# se8.net
KiCad netlist of a schematic drawn in EAGLE
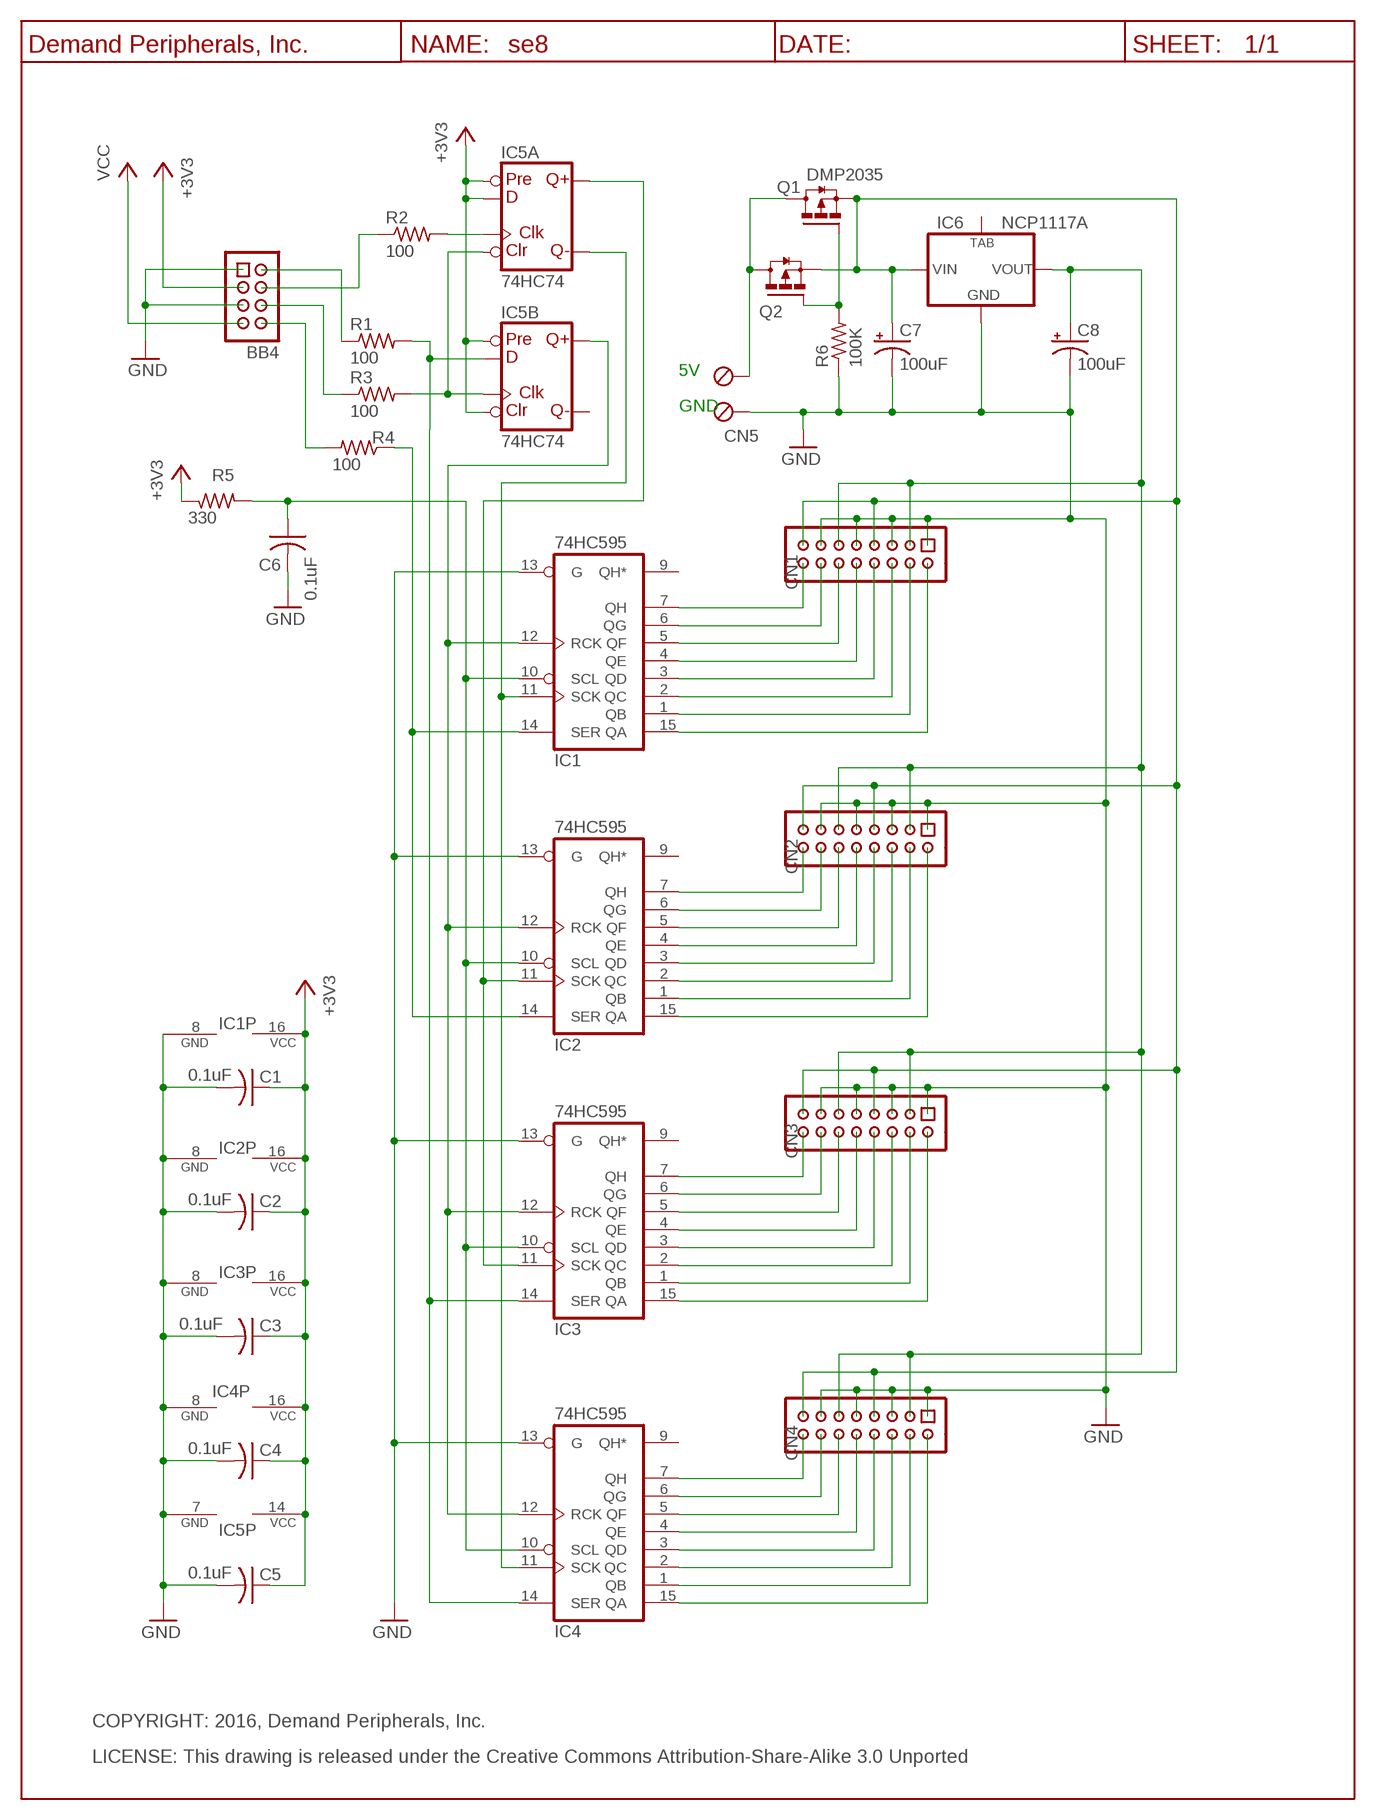
[diagram p0: schematic, sheet 1]

(export (version "E")
  (design (tool "Eeschema 10.0.6"))
  (components
    (comp (ref "BB4")
      (value "BB4 Header")
      (footprint "eagle-import:HDR-4X2")
      (libsource (lib "eagle-import") (part "HDR-4X2-SHR"))
    )
    (comp (ref "C1")
      (value "0.1uF")
      (footprint "eagle-import:C0603")
      (libsource (lib "eagle-import") (part "C0.1UF_C0603"))
    )
    (comp (ref "C2")
      (value "0.1uF")
      (footprint "eagle-import:C0603")
      (libsource (lib "eagle-import") (part "C0.1UF_C0603"))
    )
    (comp (ref "C3")
      (value "0.1uF")
      (footprint "eagle-import:C0603")
      (libsource (lib "eagle-import") (part "C0.1UF_C0603"))
    )
    (comp (ref "C4")
      (value "0.1uF")
      (footprint "eagle-import:C0603")
      (libsource (lib "eagle-import") (part "C0.1UF_C0603"))
    )
    (comp (ref "C5")
      (value "0.1uF")
      (footprint "eagle-import:C0603")
      (libsource (lib "eagle-import") (part "C0.1UF_C0603"))
    )
    (comp (ref "C6")
      (value "0.1uF")
      (footprint "eagle-import:C0603")
      (libsource (lib "eagle-import") (part "C0.1UF_C0603"))
    )
    (comp (ref "C7")
      (value "100uF")
      (footprint "eagle-import:E3.5-8")
      (libsource (lib "eagle-import") (part "C100UF35V_E3.5-8"))
    )
    (comp (ref "C8")
      (value "100uF")
      (footprint "eagle-import:E3.5-8")
      (libsource (lib "eagle-import") (part "C100UF35V_E3.5-8"))
    )
    (comp (ref "CN1")
      (value "HDR-8X2-SHR")
      (footprint "eagle-import:HDR-8X2")
      (libsource (lib "eagle-import") (part "HDR-8X2-SHR"))
    )
    (comp (ref "CN2")
      (value "HDR-8X2-SHR")
      (footprint "eagle-import:HDR-8X2")
      (libsource (lib "eagle-import") (part "HDR-8X2-SHR"))
    )
    (comp (ref "CN3")
      (value "HDR-8X2-SHR")
      (footprint "eagle-import:HDR-8X2")
      (libsource (lib "eagle-import") (part "HDR-8X2-SHR"))
    )
    (comp (ref "CN4")
      (value "HDR-8X2-SHR")
      (footprint "eagle-import:HDR-8X2")
      (libsource (lib "eagle-import") (part "HDR-8X2-SHR"))
    )
    (comp (ref "CN5")
      (value "TBLK-5.08-X2")
      (footprint "eagle-import:TBLK-5.08-X2")
      (libsource (lib "eagle-import") (part "TBLK-5.08-X2"))
    )
    (comp (ref "IC1")
      (value "74HC595")
      (footprint "eagle-import:SO16")
      (libsource (lib "eagle-import") (part "74595"))
    )
    (comp (ref "IC2")
      (value "74HC595")
      (footprint "eagle-import:SO16")
      (libsource (lib "eagle-import") (part "74595"))
    )
    (comp (ref "IC3")
      (value "74HC595")
      (footprint "eagle-import:SO16")
      (libsource (lib "eagle-import") (part "74595"))
    )
    (comp (ref "IC4")
      (value "74HC595")
      (footprint "eagle-import:SO16")
      (libsource (lib "eagle-import") (part "74595"))
    )
    (comp (ref "IC5")
      (value "74HC74")
      (footprint "eagle-import:SO14")
      (libsource (lib "eagle-import") (part "74AHC74"))
    )
    (comp (ref "IC6")
      (value "NCP1117A")
      (footprint "eagle-import:SOT223")
      (libsource (lib "eagle-import") (part "LM1117A"))
    )
    (comp (ref "Q1")
      (value "DMP2035")
      (footprint "eagle-import:SOT23")
      (libsource (lib "eagle-import") (part "DMP2035"))
    )
    (comp (ref "Q2")
      (value "DMP2035")
      (footprint "eagle-import:SOT23")
      (libsource (lib "eagle-import") (part "DMP2035"))
    )
    (comp (ref "R1")
      (value "100")
      (footprint "eagle-import:R0603")
      (libsource (lib "eagle-import") (part "R100_R0603"))
    )
    (comp (ref "R2")
      (value "100")
      (footprint "eagle-import:R0603")
      (libsource (lib "eagle-import") (part "R100_R0603"))
    )
    (comp (ref "R3")
      (value "100")
      (footprint "eagle-import:R0603")
      (libsource (lib "eagle-import") (part "R100_R0603"))
    )
    (comp (ref "R4")
      (value "100")
      (footprint "eagle-import:R0603")
      (libsource (lib "eagle-import") (part "R100_R0603"))
    )
    (comp (ref "R5")
      (value "330")
      (footprint "eagle-import:R0603")
      (libsource (lib "eagle-import") (part "R330_R0603"))
    )
    (comp (ref "R6")
      (value "100K")
      (footprint "eagle-import:R0603")
      (libsource (lib "eagle-import") (part "R100K_R0603"))
    )
    (comp (ref "U$2")
      (value "DP_FRAME_P")
      (footprint "eagle-import:P_FRAME")
      (libsource (lib "eagle-import") (part "DP_FRAME_P"))
    )
  )
  (nets
    (net (code "1") (name "+3V3") (class "Default")
      (node (ref "BB4") (pin "3") (pinfunction "3_3") (pintype "passive"))
      (node (ref "C1") (pin "1") (pinfunction "1_1") (pintype "passive"))
      (node (ref "C2") (pin "1") (pinfunction "1_1") (pintype "passive"))
      (node (ref "C3") (pin "1") (pinfunction "1_1") (pintype "passive"))
      (node (ref "C4") (pin "1") (pinfunction "1_1") (pintype "passive"))
      (node (ref "C5") (pin "1") (pinfunction "1_1") (pintype "passive"))
      (node (ref "IC1") (pin "16") (pinfunction "VCC_16") (pintype "power_in"))
      (node (ref "IC2") (pin "16") (pinfunction "VCC_16") (pintype "power_in"))
      (node (ref "IC3") (pin "16") (pinfunction "VCC_16") (pintype "power_in"))
      (node (ref "IC4") (pin "16") (pinfunction "VCC_16") (pintype "power_in"))
      (node (ref "IC5") (pin "10") (pinfunction "PRE_10") (pintype "input"))
      (node (ref "IC5") (pin "13") (pinfunction "CLR_13") (pintype "input"))
      (node (ref "IC5") (pin "14") (pinfunction "VCC_14") (pintype "power_in"))
      (node (ref "IC5") (pin "2") (pinfunction "D_2") (pintype "input"))
      (node (ref "IC5") (pin "4") (pinfunction "PRE_4") (pintype "input"))
      (node (ref "R5") (pin "1") (pinfunction "1_1") (pintype "passive"))
    )
    (net (code "2") (name "GND") (class "Default")
      (node (ref "BB4") (pin "1") (pinfunction "1_1") (pintype "passive"))
      (node (ref "BB4") (pin "5") (pinfunction "5_5") (pintype "passive"))
      (node (ref "C1") (pin "2") (pinfunction "2_2") (pintype "passive"))
      (node (ref "C2") (pin "2") (pinfunction "2_2") (pintype "passive"))
      (node (ref "C3") (pin "2") (pinfunction "2_2") (pintype "passive"))
      (node (ref "C4") (pin "2") (pinfunction "2_2") (pintype "passive"))
      (node (ref "C5") (pin "2") (pinfunction "2_2") (pintype "passive"))
      (node (ref "C6") (pin "2") (pinfunction "2_2") (pintype "passive"))
      (node (ref "C7") (pin "-") (pinfunction "-_-") (pintype "passive"))
      (node (ref "C8") (pin "-") (pinfunction "-_-") (pintype "passive"))
      (node (ref "CN1") (pin "1") (pinfunction "1_1") (pintype "passive"))
      (node (ref "CN1") (pin "13") (pinfunction "13_13") (pintype "passive"))
      (node (ref "CN1") (pin "5") (pinfunction "5_5") (pintype "passive"))
      (node (ref "CN1") (pin "9") (pinfunction "9_9") (pintype "passive"))
      (node (ref "CN2") (pin "1") (pinfunction "1_1") (pintype "passive"))
      (node (ref "CN2") (pin "13") (pinfunction "13_13") (pintype "passive"))
      (node (ref "CN2") (pin "5") (pinfunction "5_5") (pintype "passive"))
      (node (ref "CN2") (pin "9") (pinfunction "9_9") (pintype "passive"))
      (node (ref "CN3") (pin "1") (pinfunction "1_1") (pintype "passive"))
      (node (ref "CN3") (pin "13") (pinfunction "13_13") (pintype "passive"))
      (node (ref "CN3") (pin "5") (pinfunction "5_5") (pintype "passive"))
      (node (ref "CN3") (pin "9") (pinfunction "9_9") (pintype "passive"))
      (node (ref "CN4") (pin "1") (pinfunction "1_1") (pintype "passive"))
      (node (ref "CN4") (pin "13") (pinfunction "13_13") (pintype "passive"))
      (node (ref "CN4") (pin "5") (pinfunction "5_5") (pintype "passive"))
      (node (ref "CN4") (pin "9") (pinfunction "9_9") (pintype "passive"))
      (node (ref "CN5") (pin "1") (pinfunction "KL_1") (pintype "passive"))
      (node (ref "IC1") (pin "13") (pinfunction "G_13") (pintype "input"))
      (node (ref "IC1") (pin "8") (pinfunction "GND_8") (pintype "power_in"))
      (node (ref "IC2") (pin "13") (pinfunction "G_13") (pintype "input"))
      (node (ref "IC2") (pin "8") (pinfunction "GND_8") (pintype "power_in"))
      (node (ref "IC3") (pin "13") (pinfunction "G_13") (pintype "input"))
      (node (ref "IC3") (pin "8") (pinfunction "GND_8") (pintype "power_in"))
      (node (ref "IC4") (pin "13") (pinfunction "G_13") (pintype "input"))
      (node (ref "IC4") (pin "8") (pinfunction "GND_8") (pintype "power_in"))
      (node (ref "IC5") (pin "7") (pinfunction "GND_7") (pintype "power_in"))
      (node (ref "IC6") (pin "1") (pinfunction "GND_1") (pintype "input"))
      (node (ref "R6") (pin "1") (pinfunction "1_1") (pintype "passive"))
    )
    (net (code "3") (name "Net-(BB4-Pad2)") (class "Default")
      (node (ref "BB4") (pin "2") (pinfunction "2_2") (pintype "passive"))
      (node (ref "R1") (pin "1") (pinfunction "1_1") (pintype "passive"))
    )
    (net (code "4") (name "Net-(BB4-Pad4)") (class "Default")
      (node (ref "BB4") (pin "4") (pinfunction "4_4") (pintype "passive"))
      (node (ref "R2") (pin "1") (pinfunction "1_1") (pintype "passive"))
    )
    (net (code "5") (name "Net-(BB4-Pad6)") (class "Default")
      (node (ref "BB4") (pin "6") (pinfunction "6_6") (pintype "passive"))
      (node (ref "R3") (pin "1") (pinfunction "1_1") (pintype "passive"))
    )
    (net (code "6") (name "Net-(BB4-Pad8)") (class "Default")
      (node (ref "BB4") (pin "8") (pinfunction "8_8") (pintype "passive"))
      (node (ref "R4") (pin "2") (pinfunction "2_2") (pintype "passive"))
    )
    (net (code "7") (name "Net-(CN5-KL1)") (class "Default")
      (node (ref "CN5") (pin "2") (pinfunction "KL1_2") (pintype "passive"))
      (node (ref "Q1") (pin "2") (pinfunction "D_2") (pintype "passive"))
      (node (ref "Q2") (pin "2") (pinfunction "D_2") (pintype "passive"))
    )
    (net (code "8") (name "Net-(IC1A-QA)") (class "Default")
      (node (ref "CN1") (pin "2") (pinfunction "2_2") (pintype "passive"))
      (node (ref "IC1") (pin "15") (pinfunction "QA_15") (pintype "tri_state"))
    )
    (net (code "9") (name "Net-(IC1A-QB)") (class "Default")
      (node (ref "CN1") (pin "4") (pinfunction "4_4") (pintype "passive"))
      (node (ref "IC1") (pin "1") (pinfunction "QB_1") (pintype "tri_state"))
    )
    (net (code "10") (name "Net-(IC1A-QC)") (class "Default")
      (node (ref "CN1") (pin "6") (pinfunction "6_6") (pintype "passive"))
      (node (ref "IC1") (pin "2") (pinfunction "QC_2") (pintype "tri_state"))
    )
    (net (code "11") (name "Net-(IC1A-QD)") (class "Default")
      (node (ref "CN1") (pin "8") (pinfunction "8_8") (pintype "passive"))
      (node (ref "IC1") (pin "3") (pinfunction "QD_3") (pintype "tri_state"))
    )
    (net (code "12") (name "Net-(IC1A-QE)") (class "Default")
      (node (ref "CN1") (pin "10") (pinfunction "10_10") (pintype "passive"))
      (node (ref "IC1") (pin "4") (pinfunction "QE_4") (pintype "tri_state"))
    )
    (net (code "13") (name "Net-(IC1A-QF)") (class "Default")
      (node (ref "CN1") (pin "12") (pinfunction "12_12") (pintype "passive"))
      (node (ref "IC1") (pin "5") (pinfunction "QF_5") (pintype "tri_state"))
    )
    (net (code "14") (name "Net-(IC1A-QG)") (class "Default")
      (node (ref "CN1") (pin "14") (pinfunction "14_14") (pintype "passive"))
      (node (ref "IC1") (pin "6") (pinfunction "QG_6") (pintype "tri_state"))
    )
    (net (code "15") (name "Net-(IC1A-QH)") (class "Default")
      (node (ref "CN1") (pin "16") (pinfunction "16_16") (pintype "passive"))
      (node (ref "IC1") (pin "7") (pinfunction "QH_7") (pintype "tri_state"))
    )
    (net (code "16") (name "Net-(IC1A-RCK)") (class "Default")
      (node (ref "IC1") (pin "12") (pinfunction "RCK_12") (pintype "input"))
      (node (ref "IC2") (pin "12") (pinfunction "RCK_12") (pintype "input"))
      (node (ref "IC3") (pin "12") (pinfunction "RCK_12") (pintype "input"))
      (node (ref "IC4") (pin "12") (pinfunction "RCK_12") (pintype "input"))
      (node (ref "IC5") (pin "9") (pinfunction "Q_9") (pintype "output"))
    )
    (net (code "17") (name "Net-(IC1A-SCK)") (class "Default")
      (node (ref "IC1") (pin "11") (pinfunction "SCK_11") (pintype "input"))
      (node (ref "IC4") (pin "11") (pinfunction "SCK_11") (pintype "input"))
      (node (ref "IC5") (pin "6") (pinfunction "~{Q}_6") (pintype "output"))
    )
    (net (code "18") (name "Net-(IC1A-SCL)") (class "Default")
      (node (ref "C6") (pin "1") (pinfunction "1_1") (pintype "passive"))
      (node (ref "IC1") (pin "10") (pinfunction "SCL_10") (pintype "input"))
      (node (ref "IC2") (pin "10") (pinfunction "SCL_10") (pintype "input"))
      (node (ref "IC3") (pin "10") (pinfunction "SCL_10") (pintype "input"))
      (node (ref "IC4") (pin "10") (pinfunction "SCL_10") (pintype "input"))
      (node (ref "R5") (pin "2") (pinfunction "2_2") (pintype "passive"))
    )
    (net (code "19") (name "Net-(IC1A-SER)") (class "Default")
      (node (ref "IC1") (pin "14") (pinfunction "SER_14") (pintype "input"))
      (node (ref "IC2") (pin "14") (pinfunction "SER_14") (pintype "input"))
      (node (ref "R4") (pin "1") (pinfunction "1_1") (pintype "passive"))
    )
    (net (code "20") (name "Net-(IC2A-QA)") (class "Default")
      (node (ref "CN2") (pin "2") (pinfunction "2_2") (pintype "passive"))
      (node (ref "IC2") (pin "15") (pinfunction "QA_15") (pintype "tri_state"))
    )
    (net (code "21") (name "Net-(IC2A-QB)") (class "Default")
      (node (ref "CN2") (pin "4") (pinfunction "4_4") (pintype "passive"))
      (node (ref "IC2") (pin "1") (pinfunction "QB_1") (pintype "tri_state"))
    )
    (net (code "22") (name "Net-(IC2A-QC)") (class "Default")
      (node (ref "CN2") (pin "6") (pinfunction "6_6") (pintype "passive"))
      (node (ref "IC2") (pin "2") (pinfunction "QC_2") (pintype "tri_state"))
    )
    (net (code "23") (name "Net-(IC2A-QD)") (class "Default")
      (node (ref "CN2") (pin "8") (pinfunction "8_8") (pintype "passive"))
      (node (ref "IC2") (pin "3") (pinfunction "QD_3") (pintype "tri_state"))
    )
    (net (code "24") (name "Net-(IC2A-QE)") (class "Default")
      (node (ref "CN2") (pin "10") (pinfunction "10_10") (pintype "passive"))
      (node (ref "IC2") (pin "4") (pinfunction "QE_4") (pintype "tri_state"))
    )
    (net (code "25") (name "Net-(IC2A-QF)") (class "Default")
      (node (ref "CN2") (pin "12") (pinfunction "12_12") (pintype "passive"))
      (node (ref "IC2") (pin "5") (pinfunction "QF_5") (pintype "tri_state"))
    )
    (net (code "26") (name "Net-(IC2A-QG)") (class "Default")
      (node (ref "CN2") (pin "14") (pinfunction "14_14") (pintype "passive"))
      (node (ref "IC2") (pin "6") (pinfunction "QG_6") (pintype "tri_state"))
    )
    (net (code "27") (name "Net-(IC2A-QH)") (class "Default")
      (node (ref "CN2") (pin "16") (pinfunction "16_16") (pintype "passive"))
      (node (ref "IC2") (pin "7") (pinfunction "QH_7") (pintype "tri_state"))
    )
    (net (code "28") (name "Net-(IC2A-SCK)") (class "Default")
      (node (ref "IC2") (pin "11") (pinfunction "SCK_11") (pintype "input"))
      (node (ref "IC3") (pin "11") (pinfunction "SCK_11") (pintype "input"))
      (node (ref "IC5") (pin "5") (pinfunction "Q_5") (pintype "output"))
    )
    (net (code "29") (name "Net-(IC3A-QA)") (class "Default")
      (node (ref "CN3") (pin "2") (pinfunction "2_2") (pintype "passive"))
      (node (ref "IC3") (pin "15") (pinfunction "QA_15") (pintype "tri_state"))
    )
    (net (code "30") (name "Net-(IC3A-QB)") (class "Default")
      (node (ref "CN3") (pin "4") (pinfunction "4_4") (pintype "passive"))
      (node (ref "IC3") (pin "1") (pinfunction "QB_1") (pintype "tri_state"))
    )
    (net (code "31") (name "Net-(IC3A-QC)") (class "Default")
      (node (ref "CN3") (pin "6") (pinfunction "6_6") (pintype "passive"))
      (node (ref "IC3") (pin "2") (pinfunction "QC_2") (pintype "tri_state"))
    )
    (net (code "32") (name "Net-(IC3A-QD)") (class "Default")
      (node (ref "CN3") (pin "8") (pinfunction "8_8") (pintype "passive"))
      (node (ref "IC3") (pin "3") (pinfunction "QD_3") (pintype "tri_state"))
    )
    (net (code "33") (name "Net-(IC3A-QE)") (class "Default")
      (node (ref "CN3") (pin "10") (pinfunction "10_10") (pintype "passive"))
      (node (ref "IC3") (pin "4") (pinfunction "QE_4") (pintype "tri_state"))
    )
    (net (code "34") (name "Net-(IC3A-QF)") (class "Default")
      (node (ref "CN3") (pin "12") (pinfunction "12_12") (pintype "passive"))
      (node (ref "IC3") (pin "5") (pinfunction "QF_5") (pintype "tri_state"))
    )
    (net (code "35") (name "Net-(IC3A-QG)") (class "Default")
      (node (ref "CN3") (pin "14") (pinfunction "14_14") (pintype "passive"))
      (node (ref "IC3") (pin "6") (pinfunction "QG_6") (pintype "tri_state"))
    )
    (net (code "36") (name "Net-(IC3A-QH)") (class "Default")
      (node (ref "CN3") (pin "16") (pinfunction "16_16") (pintype "passive"))
      (node (ref "IC3") (pin "7") (pinfunction "QH_7") (pintype "tri_state"))
    )
    (net (code "37") (name "Net-(IC3A-SER)") (class "Default")
      (node (ref "IC3") (pin "14") (pinfunction "SER_14") (pintype "input"))
      (node (ref "IC4") (pin "14") (pinfunction "SER_14") (pintype "input"))
      (node (ref "IC5") (pin "12") (pinfunction "D_12") (pintype "input"))
      (node (ref "R1") (pin "2") (pinfunction "2_2") (pintype "passive"))
    )
    (net (code "38") (name "Net-(IC4A-QA)") (class "Default")
      (node (ref "CN4") (pin "2") (pinfunction "2_2") (pintype "passive"))
      (node (ref "IC4") (pin "15") (pinfunction "QA_15") (pintype "tri_state"))
    )
    (net (code "39") (name "Net-(IC4A-QB)") (class "Default")
      (node (ref "CN4") (pin "4") (pinfunction "4_4") (pintype "passive"))
      (node (ref "IC4") (pin "1") (pinfunction "QB_1") (pintype "tri_state"))
    )
    (net (code "40") (name "Net-(IC4A-QC)") (class "Default")
      (node (ref "CN4") (pin "6") (pinfunction "6_6") (pintype "passive"))
      (node (ref "IC4") (pin "2") (pinfunction "QC_2") (pintype "tri_state"))
    )
    (net (code "41") (name "Net-(IC4A-QD)") (class "Default")
      (node (ref "CN4") (pin "8") (pinfunction "8_8") (pintype "passive"))
      (node (ref "IC4") (pin "3") (pinfunction "QD_3") (pintype "tri_state"))
    )
    (net (code "42") (name "Net-(IC4A-QE)") (class "Default")
      (node (ref "CN4") (pin "10") (pinfunction "10_10") (pintype "passive"))
      (node (ref "IC4") (pin "4") (pinfunction "QE_4") (pintype "tri_state"))
    )
    (net (code "43") (name "Net-(IC4A-QF)") (class "Default")
      (node (ref "CN4") (pin "12") (pinfunction "12_12") (pintype "passive"))
      (node (ref "IC4") (pin "5") (pinfunction "QF_5") (pintype "tri_state"))
    )
    (net (code "44") (name "Net-(IC4A-QG)") (class "Default")
      (node (ref "CN4") (pin "14") (pinfunction "14_14") (pintype "passive"))
      (node (ref "IC4") (pin "6") (pinfunction "QG_6") (pintype "tri_state"))
    )
    (net (code "45") (name "Net-(IC4A-QH)") (class "Default")
      (node (ref "CN4") (pin "16") (pinfunction "16_16") (pintype "passive"))
      (node (ref "IC4") (pin "7") (pinfunction "QH_7") (pintype "tri_state"))
    )
    (net (code "46") (name "Net-(IC5A-CLK)") (class "Default")
      (node (ref "IC5") (pin "3") (pinfunction "CLK_3") (pintype "input"))
      (node (ref "R2") (pin "2") (pinfunction "2_2") (pintype "passive"))
    )
    (net (code "47") (name "Net-(IC5A-CLR)") (class "Default")
      (node (ref "IC5") (pin "1") (pinfunction "CLR_1") (pintype "input"))
      (node (ref "IC5") (pin "11") (pinfunction "CLK_11") (pintype "input"))
      (node (ref "R3") (pin "2") (pinfunction "2_2") (pintype "passive"))
    )
    (net (code "48") (name "Net-(IC6-IN)") (class "Default")
      (node (ref "C7") (pin "+") (pinfunction "+_+") (pintype "passive"))
      (node (ref "CN1") (pin "15") (pinfunction "15_15") (pintype "passive"))
      (node (ref "CN1") (pin "7") (pinfunction "7_7") (pintype "passive"))
      (node (ref "CN2") (pin "15") (pinfunction "15_15") (pintype "passive"))
      (node (ref "CN2") (pin "7") (pinfunction "7_7") (pintype "passive"))
      (node (ref "CN3") (pin "15") (pinfunction "15_15") (pintype "passive"))
      (node (ref "CN3") (pin "7") (pinfunction "7_7") (pintype "passive"))
      (node (ref "CN4") (pin "15") (pinfunction "15_15") (pintype "passive"))
      (node (ref "CN4") (pin "7") (pinfunction "7_7") (pintype "passive"))
      (node (ref "IC6") (pin "3") (pinfunction "IN_3") (pintype "input"))
      (node (ref "Q1") (pin "3") (pinfunction "S_3") (pintype "passive"))
      (node (ref "Q2") (pin "3") (pinfunction "S_3") (pintype "passive"))
    )
    (net (code "49") (name "Net-(IC6-OUT)") (class "Default")
      (node (ref "C8") (pin "+") (pinfunction "+_+") (pintype "passive"))
      (node (ref "CN1") (pin "11") (pinfunction "11_11") (pintype "passive"))
      (node (ref "CN1") (pin "3") (pinfunction "3_3") (pintype "passive"))
      (node (ref "CN2") (pin "11") (pinfunction "11_11") (pintype "passive"))
      (node (ref "CN2") (pin "3") (pinfunction "3_3") (pintype "passive"))
      (node (ref "CN3") (pin "11") (pinfunction "11_11") (pintype "passive"))
      (node (ref "CN3") (pin "3") (pinfunction "3_3") (pintype "passive"))
      (node (ref "CN4") (pin "11") (pinfunction "11_11") (pintype "passive"))
      (node (ref "CN4") (pin "3") (pinfunction "3_3") (pintype "passive"))
      (node (ref "IC6") (pin "2") (pinfunction "OUT_2") (pintype "passive"))
    )
    (net (code "50") (name "Net-(Q1-G)") (class "Default")
      (node (ref "Q1") (pin "1") (pinfunction "G_1") (pintype "passive"))
      (node (ref "Q2") (pin "1") (pinfunction "G_1") (pintype "passive"))
      (node (ref "R6") (pin "2") (pinfunction "2_2") (pintype "passive"))
    )
    (net (code "51") (name "VCC") (class "Default")
      (node (ref "BB4") (pin "7") (pinfunction "7_7") (pintype "passive"))
    )
    (net (code "52") (name "unconnected-(IC1A-QH*-Pad9)") (class "Default")
      (node (ref "IC1") (pin "9") (pinfunction "QH*_9") (pintype "tri_state"))
    )
    (net (code "53") (name "unconnected-(IC2A-QH*-Pad9)") (class "Default")
      (node (ref "IC2") (pin "9") (pinfunction "QH*_9") (pintype "tri_state"))
    )
    (net (code "54") (name "unconnected-(IC3A-QH*-Pad9)") (class "Default")
      (node (ref "IC3") (pin "9") (pinfunction "QH*_9") (pintype "tri_state"))
    )
    (net (code "55") (name "unconnected-(IC4A-QH*-Pad9)") (class "Default")
      (node (ref "IC4") (pin "9") (pinfunction "QH*_9") (pintype "tri_state"))
    )
    (net (code "56") (name "unconnected-(IC5B-~{Q}-Pad8)") (class "Default")
      (node (ref "IC5") (pin "8") (pinfunction "~{Q}_8") (pintype "output"))
    )
    (net (code "57") (name "unconnected-(IC6-TAB-Pad4)") (class "Default")
      (node (ref "IC6") (pin "4") (pinfunction "TAB_4") (pintype "bidirectional"))
    )
  )
)
